# tx.net
KiCad netlist of a schematic drawn in EAGLE
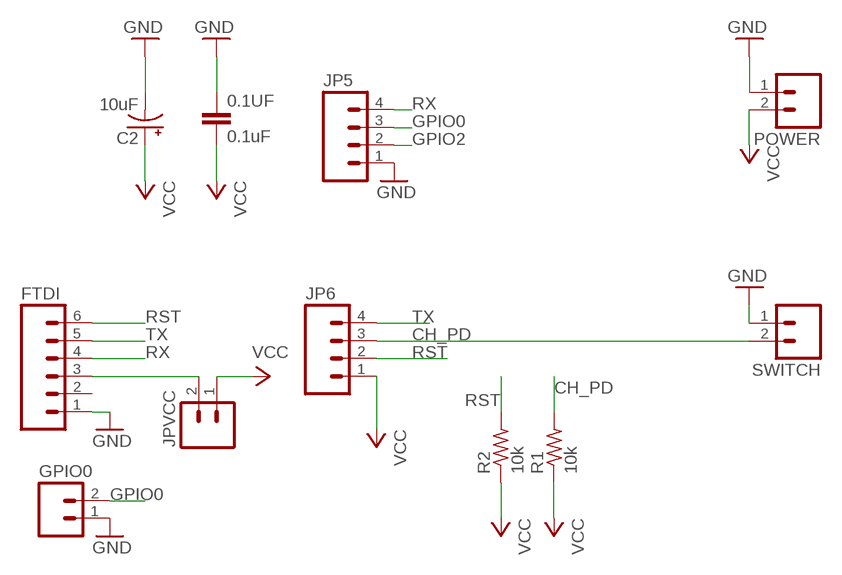
[diagram p0: schematic, sheet 1]

(export (version "E")
  (design (tool "Eeschema 10.0.6"))
  (components
    (comp (ref "0.1UF")
      (value "0.1uF")
      (footprint "eagle-import:0603-CAP")
      (libsource (lib "eagle-import") (part "0.1UF-100V-10%(0603)"))
    )
    (comp (ref "C2")
      (value "10uF")
      (footprint "eagle-import:EIA6032")
      (libsource (lib "eagle-import") (part "CAP_POL6032"))
    )
    (comp (ref "FTDI")
      (value "M06LOCK")
      (footprint "eagle-import:1X06_LOCK")
      (libsource (lib "eagle-import") (part "M06LOCK"))
    )
    (comp (ref "GPIO0")
      (value "M02PTH")
      (footprint "eagle-import:1X02")
      (libsource (lib "eagle-import") (part "M02PTH"))
    )
    (comp (ref "JP5")
      (value "M041X04_NO_SILK")
      (footprint "eagle-import:1X04_NO_SILK")
      (libsource (lib "eagle-import") (part "M041X04_NO_SILK"))
    )
    (comp (ref "JP6")
      (value "M041X04_NO_SILK")
      (footprint "eagle-import:1X04_NO_SILK")
      (libsource (lib "eagle-import") (part "M041X04_NO_SILK"))
    )
    (comp (ref "JPVCC")
      (value "M02PTH")
      (footprint "eagle-import:1X02")
      (libsource (lib "eagle-import") (part "M02PTH"))
    )
    (comp (ref "POWER")
      (value "M02PTH")
      (footprint "eagle-import:1X02")
      (libsource (lib "eagle-import") (part "M02PTH"))
    )
    (comp (ref "R1")
      (value "10k")
      (footprint "eagle-import:R0805")
      (libsource (lib "eagle-import") (part "R-US_R0805"))
    )
    (comp (ref "R2")
      (value "10k")
      (footprint "eagle-import:R0805")
      (libsource (lib "eagle-import") (part "R-US_R0805"))
    )
    (comp (ref "SWITCH")
      (value "M02PTH")
      (footprint "eagle-import:1X02")
      (libsource (lib "eagle-import") (part "M02PTH"))
    )
  )
  (nets
    (net (code "1") (name "/CH_PD") (class "Default")
      (node (ref "JP6") (pin "3") (pinfunction "3_3") (pintype "passive"))
      (node (ref "R1") (pin "2") (pinfunction "2_2") (pintype "passive"))
      (node (ref "SWITCH") (pin "2") (pinfunction "2_2") (pintype "passive"))
    )
    (net (code "2") (name "/GPIO0") (class "Default")
      (node (ref "GPIO0") (pin "2") (pinfunction "2_2") (pintype "passive"))
      (node (ref "JP5") (pin "3") (pinfunction "3_3") (pintype "passive"))
    )
    (net (code "3") (name "/GPIO2") (class "Default")
      (node (ref "JP5") (pin "2") (pinfunction "2_2") (pintype "passive"))
    )
    (net (code "4") (name "/RST") (class "Default")
      (node (ref "FTDI") (pin "6") (pinfunction "6_6") (pintype "passive"))
      (node (ref "JP6") (pin "2") (pinfunction "2_2") (pintype "passive"))
      (node (ref "R2") (pin "2") (pinfunction "2_2") (pintype "passive"))
    )
    (net (code "5") (name "/RX") (class "Default")
      (node (ref "FTDI") (pin "4") (pinfunction "4_4") (pintype "passive"))
      (node (ref "JP5") (pin "4") (pinfunction "4_4") (pintype "passive"))
    )
    (net (code "6") (name "/TX") (class "Default")
      (node (ref "FTDI") (pin "5") (pinfunction "5_5") (pintype "passive"))
      (node (ref "JP6") (pin "4") (pinfunction "4_4") (pintype "passive"))
    )
    (net (code "7") (name "GND") (class "Default")
      (node (ref "0.1UF") (pin "1") (pinfunction "1_1") (pintype "passive"))
      (node (ref "C2") (pin "P$2") (pinfunction "-_P$2") (pintype "passive"))
      (node (ref "FTDI") (pin "1") (pinfunction "1_1") (pintype "passive"))
      (node (ref "GPIO0") (pin "1") (pinfunction "1_1") (pintype "passive"))
      (node (ref "JP5") (pin "1") (pinfunction "1_1") (pintype "passive"))
      (node (ref "POWER") (pin "1") (pinfunction "1_1") (pintype "passive"))
      (node (ref "SWITCH") (pin "1") (pinfunction "1_1") (pintype "passive"))
    )
    (net (code "8") (name "Net-(FTDI-Pad3)") (class "Default")
      (node (ref "FTDI") (pin "3") (pinfunction "3_3") (pintype "passive"))
      (node (ref "JPVCC") (pin "2") (pinfunction "2_2") (pintype "passive"))
    )
    (net (code "9") (name "VCC") (class "Default")
      (node (ref "0.1UF") (pin "2") (pinfunction "2_2") (pintype "passive"))
      (node (ref "C2") (pin "P$1") (pinfunction "+_P$1") (pintype "passive"))
      (node (ref "JP6") (pin "1") (pinfunction "1_1") (pintype "passive"))
      (node (ref "JPVCC") (pin "1") (pinfunction "1_1") (pintype "passive"))
      (node (ref "POWER") (pin "2") (pinfunction "2_2") (pintype "passive"))
      (node (ref "R1") (pin "1") (pinfunction "1_1") (pintype "passive"))
      (node (ref "R2") (pin "1") (pinfunction "1_1") (pintype "passive"))
    )
    (net (code "10") (name "unconnected-(FTDI-Pad2)") (class "Default")
      (node (ref "FTDI") (pin "2") (pinfunction "2_2") (pintype "passive"))
    )
  )
)
